# LCD3_5.net
KiCad netlist of a schematic drawn in Altium Designer
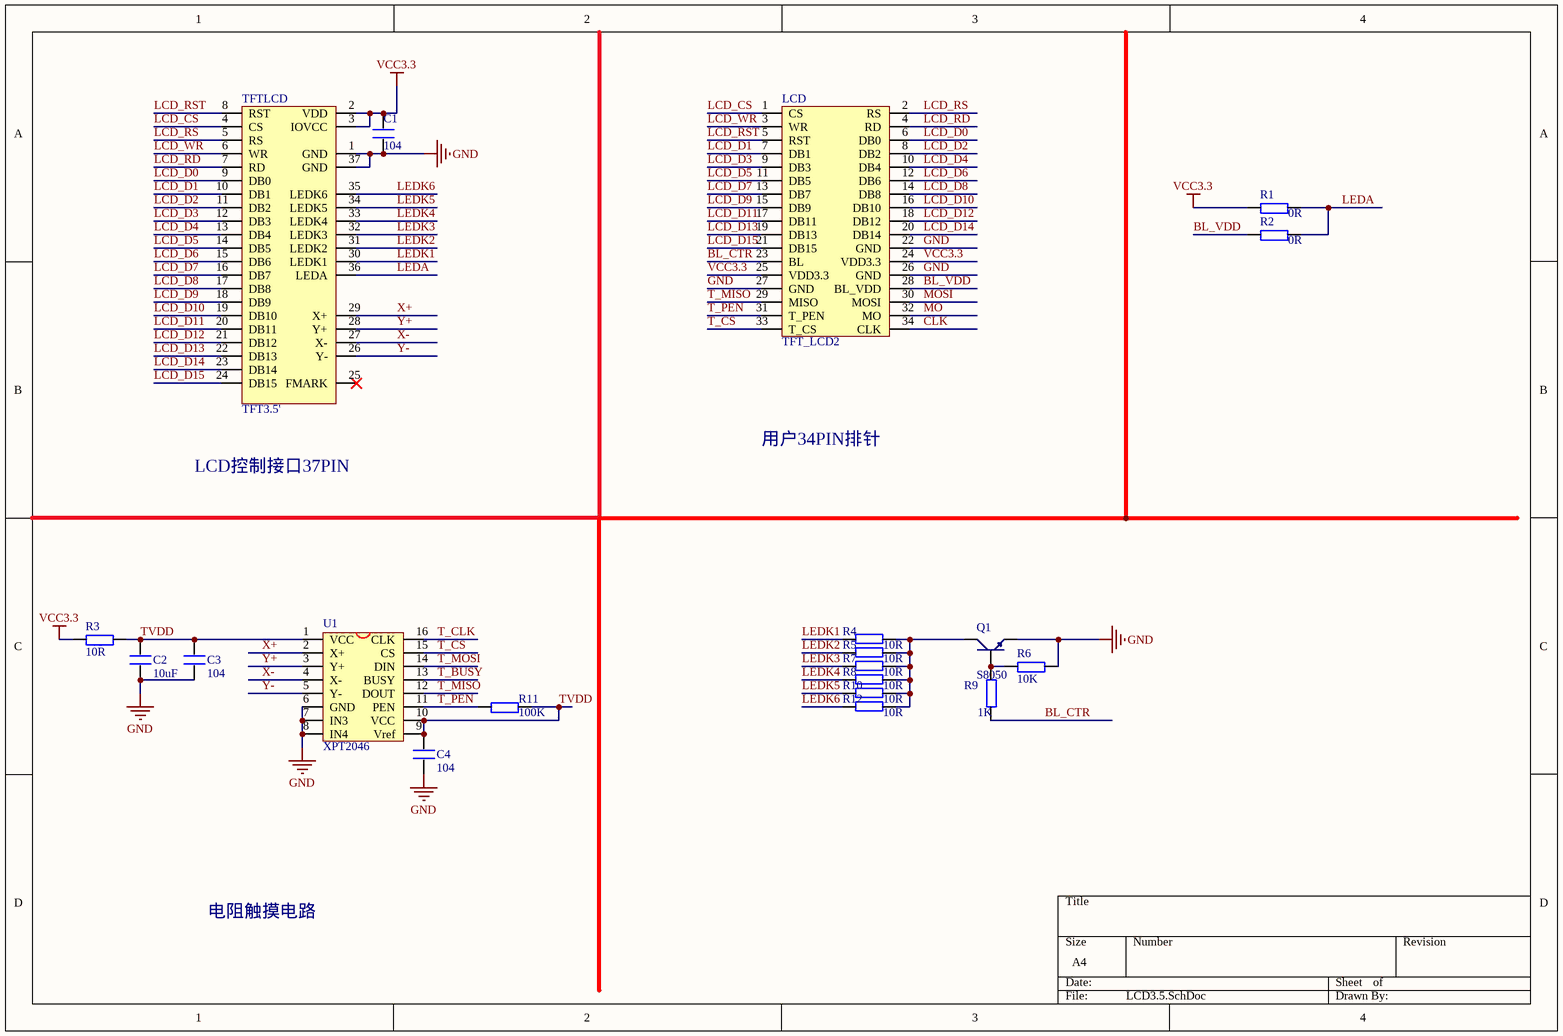
[diagram p0: LCD3.5.SchDoc]

(export (version "E")
  (design (tool "Eeschema 10.0.6"))
  (components
    (comp (ref "C1") (value "104") (footprint "0603P") (libsource (lib "3.5TFTLCD") (part "C")))
    (comp (ref "C2") (value "10uF") (footprint "0603P") (libsource (lib "3.5TFTLCD") (part "C")))
    (comp (ref "C3") (value "104") (footprint "0603P") (libsource (lib "3.5TFTLCD") (part "C")))
    (comp (ref "C4") (value "104") (footprint "0603P") (libsource (lib "3.5TFTLCD") (part "C")))
    (comp (ref "LCD")
      (value "TFT_LCD2")
      (footprint "DB2*17-3.5")
      (libsource (lib "3.5TFTLCD") (part "TFT_LCD2"))
    )
    (comp (ref "Q1")
      (value "S8050")
      (footprint "SOT-23R")
      (description "8050/BCW846/BCW847")
      (libsource (lib "3.5TFTLCD") (part "NPN"))
    )
    (comp (ref "R1") (value "0R") (footprint "0603P") (libsource (lib "3.5TFTLCD") (part "R")))
    (comp (ref "R2") (value "0R") (footprint "0603P") (libsource (lib "3.5TFTLCD") (part "R")))
    (comp (ref "R3") (value "10R") (footprint "0603P") (libsource (lib "3.5TFTLCD") (part "R")))
    (comp (ref "R4") (value "10R") (footprint "0603P") (libsource (lib "3.5TFTLCD") (part "R")))
    (comp (ref "R5") (value "10R") (footprint "0603P") (libsource (lib "3.5TFTLCD") (part "R")))
    (comp (ref "R6") (value "10K") (footprint "0603P") (libsource (lib "3.5TFTLCD") (part "R")))
    (comp (ref "R7") (value "10R") (footprint "0603P") (libsource (lib "3.5TFTLCD") (part "R")))
    (comp (ref "R8") (value "10R") (footprint "0603P") (libsource (lib "3.5TFTLCD") (part "R")))
    (comp (ref "R9") (value "1K") (footprint "0603P") (libsource (lib "3.5TFTLCD") (part "R")))
    (comp (ref "R10") (value "10R") (footprint "0603P") (libsource (lib "3.5TFTLCD") (part "R")))
    (comp (ref "R11") (value "100K") (footprint "0603P") (libsource (lib "3.5TFTLCD") (part "R")))
    (comp (ref "R12") (value "10R") (footprint "0603P") (libsource (lib "3.5TFTLCD") (part "R")))
    (comp (ref "TFTLCD")
      (value "TFT3.5'")
      (footprint "TFT3.5'")
      (description "3.5寸,带触摸,分辨率:480*320")
      (libsource (lib "3.5TFTLCD") (part "TFT3.5'"))
    )
    (comp (ref "U1") (value "XPT2046") (footprint "SSOP16") (libsource (lib "3.5TFTLCD") (part "ADS7843")))
  )
  (nets
    (net (code "1") (name "/BL_CTR") (class "Default")
      (node (ref "LCD") (pin "23") (pinfunction "BL_23") (pintype "passive"))
      (node (ref "R9") (pin "1") (pintype "passive"))
    )
    (net (code "2") (name "/BL_VDD") (class "Default")
      (node (ref "LCD") (pin "28") (pinfunction "BL_VDD_28") (pintype "passive"))
      (node (ref "R2") (pin "1") (pintype "passive"))
    )
    (net (code "3") (name "/CLK") (class "Default")
      (node (ref "LCD") (pin "34") (pinfunction "CLK_34") (pintype "passive"))
    )
    (net (code "4") (name "/LCD_CS") (class "Default")
      (node (ref "LCD") (pin "1") (pinfunction "CS_1") (pintype "passive"))
      (node (ref "TFTLCD") (pin "4") (pinfunction "CS_4") (pintype "passive"))
    )
    (net (code "5") (name "/LCD_D0") (class "Default")
      (node (ref "LCD") (pin "6") (pinfunction "DB0_6") (pintype "passive"))
      (node (ref "TFTLCD") (pin "9") (pinfunction "DB0_9") (pintype "passive"))
    )
    (net (code "6") (name "/LCD_D1") (class "Default")
      (node (ref "LCD") (pin "7") (pinfunction "DB1_7") (pintype "passive"))
      (node (ref "TFTLCD") (pin "10") (pinfunction "DB1_10") (pintype "passive"))
    )
    (net (code "7") (name "/LCD_D2") (class "Default")
      (node (ref "LCD") (pin "8") (pinfunction "DB2_8") (pintype "passive"))
      (node (ref "TFTLCD") (pin "11") (pinfunction "DB2_11") (pintype "passive"))
    )
    (net (code "8") (name "/LCD_D3") (class "Default")
      (node (ref "LCD") (pin "9") (pinfunction "DB3_9") (pintype "passive"))
      (node (ref "TFTLCD") (pin "12") (pinfunction "DB3_12") (pintype "passive"))
    )
    (net (code "9") (name "/LCD_D4") (class "Default")
      (node (ref "LCD") (pin "10") (pinfunction "DB4_10") (pintype "passive"))
      (node (ref "TFTLCD") (pin "13") (pinfunction "DB4_13") (pintype "passive"))
    )
    (net (code "10") (name "/LCD_D5") (class "Default")
      (node (ref "LCD") (pin "11") (pinfunction "DB5_11") (pintype "passive"))
      (node (ref "TFTLCD") (pin "14") (pinfunction "DB5_14") (pintype "passive"))
    )
    (net (code "11") (name "/LCD_D6") (class "Default")
      (node (ref "LCD") (pin "12") (pinfunction "DB6_12") (pintype "passive"))
      (node (ref "TFTLCD") (pin "15") (pinfunction "DB6_15") (pintype "passive"))
    )
    (net (code "12") (name "/LCD_D7") (class "Default")
      (node (ref "LCD") (pin "13") (pinfunction "DB7_13") (pintype "passive"))
      (node (ref "TFTLCD") (pin "16") (pinfunction "DB7_16") (pintype "passive"))
    )
    (net (code "13") (name "/LCD_D8") (class "Default")
      (node (ref "LCD") (pin "14") (pinfunction "DB8_14") (pintype "passive"))
      (node (ref "TFTLCD") (pin "17") (pinfunction "DB8_17") (pintype "passive"))
    )
    (net (code "14") (name "/LCD_D9") (class "Default")
      (node (ref "LCD") (pin "15") (pinfunction "DB9_15") (pintype "passive"))
      (node (ref "TFTLCD") (pin "18") (pinfunction "DB9_18") (pintype "passive"))
    )
    (net (code "15") (name "/LCD_D10") (class "Default")
      (node (ref "LCD") (pin "16") (pinfunction "DB10_16") (pintype "passive"))
      (node (ref "TFTLCD") (pin "19") (pinfunction "DB10_19") (pintype "passive"))
    )
    (net (code "16") (name "/LCD_D11") (class "Default")
      (node (ref "LCD") (pin "17") (pinfunction "DB11_17") (pintype "passive"))
      (node (ref "TFTLCD") (pin "20") (pinfunction "DB11_20") (pintype "passive"))
    )
    (net (code "17") (name "/LCD_D12") (class "Default")
      (node (ref "LCD") (pin "18") (pinfunction "DB12_18") (pintype "passive"))
      (node (ref "TFTLCD") (pin "21") (pinfunction "DB12_21") (pintype "passive"))
    )
    (net (code "18") (name "/LCD_D13") (class "Default")
      (node (ref "LCD") (pin "19") (pinfunction "DB13_19") (pintype "passive"))
      (node (ref "TFTLCD") (pin "22") (pinfunction "DB13_22") (pintype "passive"))
    )
    (net (code "19") (name "/LCD_D14") (class "Default")
      (node (ref "LCD") (pin "20") (pinfunction "DB14_20") (pintype "passive"))
      (node (ref "TFTLCD") (pin "23") (pinfunction "DB14_23") (pintype "passive"))
    )
    (net (code "20") (name "/LCD_D15") (class "Default")
      (node (ref "LCD") (pin "21") (pinfunction "DB15_21") (pintype "passive"))
      (node (ref "TFTLCD") (pin "24") (pinfunction "DB15_24") (pintype "passive"))
    )
    (net (code "21") (name "/LCD_RD") (class "Default")
      (node (ref "LCD") (pin "4") (pinfunction "RD_4") (pintype "passive"))
      (node (ref "TFTLCD") (pin "7") (pinfunction "RD_7") (pintype "passive"))
    )
    (net (code "22") (name "/LCD_RS") (class "Default")
      (node (ref "LCD") (pin "2") (pinfunction "RS_2") (pintype "passive"))
      (node (ref "TFTLCD") (pin "5") (pinfunction "RS_5") (pintype "passive"))
    )
    (net (code "23") (name "/LCD_RST") (class "Default")
      (node (ref "LCD") (pin "5") (pinfunction "RST_5") (pintype "passive"))
      (node (ref "TFTLCD") (pin "8") (pinfunction "RST_8") (pintype "passive"))
    )
    (net (code "24") (name "/LCD_WR") (class "Default")
      (node (ref "LCD") (pin "3") (pinfunction "WR_3") (pintype "passive"))
      (node (ref "TFTLCD") (pin "6") (pinfunction "WR_6") (pintype "passive"))
    )
    (net (code "25") (name "/LEDA") (class "Default")
      (node (ref "R1") (pin "2") (pintype "passive"))
      (node (ref "R2") (pin "2") (pintype "passive"))
      (node (ref "TFTLCD") (pin "36") (pinfunction "LEDA_36") (pintype "passive"))
    )
    (net (code "26") (name "/LEDK1") (class "Default")
      (node (ref "R4") (pin "2") (pintype "passive"))
      (node (ref "TFTLCD") (pin "30") (pinfunction "LEDK1_30") (pintype "passive"))
    )
    (net (code "27") (name "/LEDK2") (class "Default")
      (node (ref "R5") (pin "2") (pintype "passive"))
      (node (ref "TFTLCD") (pin "31") (pinfunction "LEDK2_31") (pintype "passive"))
    )
    (net (code "28") (name "/LEDK3") (class "Default")
      (node (ref "R7") (pin "2") (pintype "passive"))
      (node (ref "TFTLCD") (pin "32") (pinfunction "LEDK3_32") (pintype "passive"))
    )
    (net (code "29") (name "/LEDK4") (class "Default")
      (node (ref "R8") (pin "2") (pintype "passive"))
      (node (ref "TFTLCD") (pin "33") (pinfunction "LEDK4_33") (pintype "passive"))
    )
    (net (code "30") (name "/LEDK5") (class "Default")
      (node (ref "R10") (pin "2") (pintype "passive"))
      (node (ref "TFTLCD") (pin "34") (pinfunction "LEDK5_34") (pintype "passive"))
    )
    (net (code "31") (name "/LEDK6") (class "Default")
      (node (ref "R12") (pin "2") (pintype "passive"))
      (node (ref "TFTLCD") (pin "35") (pinfunction "LEDK6_35") (pintype "passive"))
    )
    (net (code "32") (name "/MO") (class "Default")
      (node (ref "LCD") (pin "32") (pinfunction "MO_32") (pintype "passive"))
    )
    (net (code "33") (name "/MOSI") (class "Default")
      (node (ref "LCD") (pin "30") (pinfunction "MOSI_30") (pintype "passive"))
    )
    (net (code "34") (name "/TVDD") (class "Default")
      (node (ref "C2") (pin "2") (pintype "passive"))
      (node (ref "C3") (pin "2") (pintype "passive"))
      (node (ref "C4") (pin "2") (pintype "passive"))
      (node (ref "R11") (pin "2") (pintype "passive"))
      (node (ref "R3") (pin "2") (pintype "passive"))
      (node (ref "U1") (pin "1") (pinfunction "VCC_1") (pintype "passive"))
      (node (ref "U1") (pin "10") (pinfunction "VCC_10") (pintype "passive"))
      (node (ref "U1") (pin "9") (pinfunction "Vref_9") (pintype "passive"))
    )
    (net (code "35") (name "/T_BUSY") (class "Default")
      (node (ref "U1") (pin "13") (pinfunction "BUSY_13") (pintype "passive"))
    )
    (net (code "36") (name "/T_CLK") (class "Default")
      (node (ref "U1") (pin "16") (pinfunction "CLK_16") (pintype "passive"))
    )
    (net (code "37") (name "/T_CS") (class "Default")
      (node (ref "LCD") (pin "33") (pinfunction "T_CS_33") (pintype "passive"))
      (node (ref "U1") (pin "15") (pinfunction "CS_15") (pintype "passive"))
    )
    (net (code "38") (name "/T_MISO") (class "Default")
      (node (ref "LCD") (pin "29") (pinfunction "MISO_29") (pintype "passive"))
      (node (ref "U1") (pin "12") (pinfunction "DOUT_12") (pintype "passive"))
    )
    (net (code "39") (name "/T_MOSI") (class "Default")
      (node (ref "U1") (pin "14") (pinfunction "DIN_14") (pintype "passive"))
    )
    (net (code "40") (name "/T_PEN") (class "Default")
      (node (ref "LCD") (pin "31") (pinfunction "T_PEN_31") (pintype "passive"))
      (node (ref "R11") (pin "1") (pintype "passive"))
      (node (ref "U1") (pin "11") (pinfunction "PEN_11") (pintype "passive"))
    )
    (net (code "41") (name "/X+") (class "Default")
      (node (ref "TFTLCD") (pin "29") (pinfunction "X+_29") (pintype "passive"))
      (node (ref "U1") (pin "2") (pinfunction "X+_2") (pintype "passive"))
    )
    (net (code "42") (name "/X-") (class "Default")
      (node (ref "TFTLCD") (pin "27") (pinfunction "X-_27") (pintype "passive"))
      (node (ref "U1") (pin "4") (pinfunction "X-_4") (pintype "passive"))
    )
    (net (code "43") (name "/Y+") (class "Default")
      (node (ref "TFTLCD") (pin "28") (pinfunction "Y+_28") (pintype "passive"))
      (node (ref "U1") (pin "3") (pinfunction "Y+_3") (pintype "passive"))
    )
    (net (code "44") (name "/Y-") (class "Default")
      (node (ref "TFTLCD") (pin "26") (pinfunction "Y-_26") (pintype "passive"))
      (node (ref "U1") (pin "5") (pinfunction "Y-_5") (pintype "passive"))
    )
    (net (code "45") (name "GND") (class "Default")
      (node (ref "C1") (pin "1") (pintype "passive"))
      (node (ref "C2") (pin "1") (pintype "passive"))
      (node (ref "C3") (pin "1") (pintype "passive"))
      (node (ref "C4") (pin "1") (pintype "passive"))
      (node (ref "LCD") (pin "22") (pinfunction "GND_22") (pintype "passive"))
      (node (ref "LCD") (pin "26") (pinfunction "GND_26") (pintype "passive"))
      (node (ref "LCD") (pin "27") (pinfunction "GND_27") (pintype "passive"))
      (node (ref "Q1") (pin "1") (pinfunction "E_1") (pintype "passive"))
      (node (ref "R6") (pin "2") (pintype "passive"))
      (node (ref "TFTLCD") (pin "1") (pinfunction "GND_1") (pintype "passive"))
      (node (ref "TFTLCD") (pin "37") (pinfunction "GND_37") (pintype "passive"))
      (node (ref "U1") (pin "6") (pinfunction "GND_6") (pintype "passive"))
      (node (ref "U1") (pin "7") (pinfunction "IN3_7") (pintype "passive"))
      (node (ref "U1") (pin "8") (pinfunction "IN4_8") (pintype "passive"))
    )
    (net (code "46") (name "Net-(Q1-B)") (class "Default")
      (node (ref "Q1") (pin "2") (pinfunction "B_2") (pintype "passive"))
      (node (ref "R6") (pin "1") (pintype "passive"))
      (node (ref "R9") (pin "2") (pintype "passive"))
    )
    (net (code "47") (name "Net-(Q1-C)") (class "Default")
      (node (ref "Q1") (pin "3") (pinfunction "C_3") (pintype "passive"))
      (node (ref "R10") (pin "1") (pintype "passive"))
      (node (ref "R12") (pin "1") (pintype "passive"))
      (node (ref "R4") (pin "1") (pintype "passive"))
      (node (ref "R5") (pin "1") (pintype "passive"))
      (node (ref "R7") (pin "1") (pintype "passive"))
      (node (ref "R8") (pin "1") (pintype "passive"))
    )
    (net (code "48") (name "VCC3.3") (class "Default")
      (node (ref "C1") (pin "2") (pintype "passive"))
      (node (ref "LCD") (pin "24") (pinfunction "VDD3.3_24") (pintype "passive"))
      (node (ref "LCD") (pin "25") (pinfunction "VDD3.3_25") (pintype "passive"))
      (node (ref "R1") (pin "1") (pintype "passive"))
      (node (ref "R3") (pin "1") (pintype "passive"))
      (node (ref "TFTLCD") (pin "2") (pinfunction "VDD_2") (pintype "passive"))
      (node (ref "TFTLCD") (pin "3") (pinfunction "IOVCC_3") (pintype "passive"))
    )
    (net (code "49") (name "unconnected-(TFTLCD-FMARK-Pad25)") (class "Default")
      (node (ref "TFTLCD") (pin "25") (pinfunction "FMARK_25") (pintype "passive+no_connect"))
    )
  )
)
